# Fuente_lineal_12V_-12V_5V_-_500mA.net
KiCad netlist of a schematic drawn in EAGLE
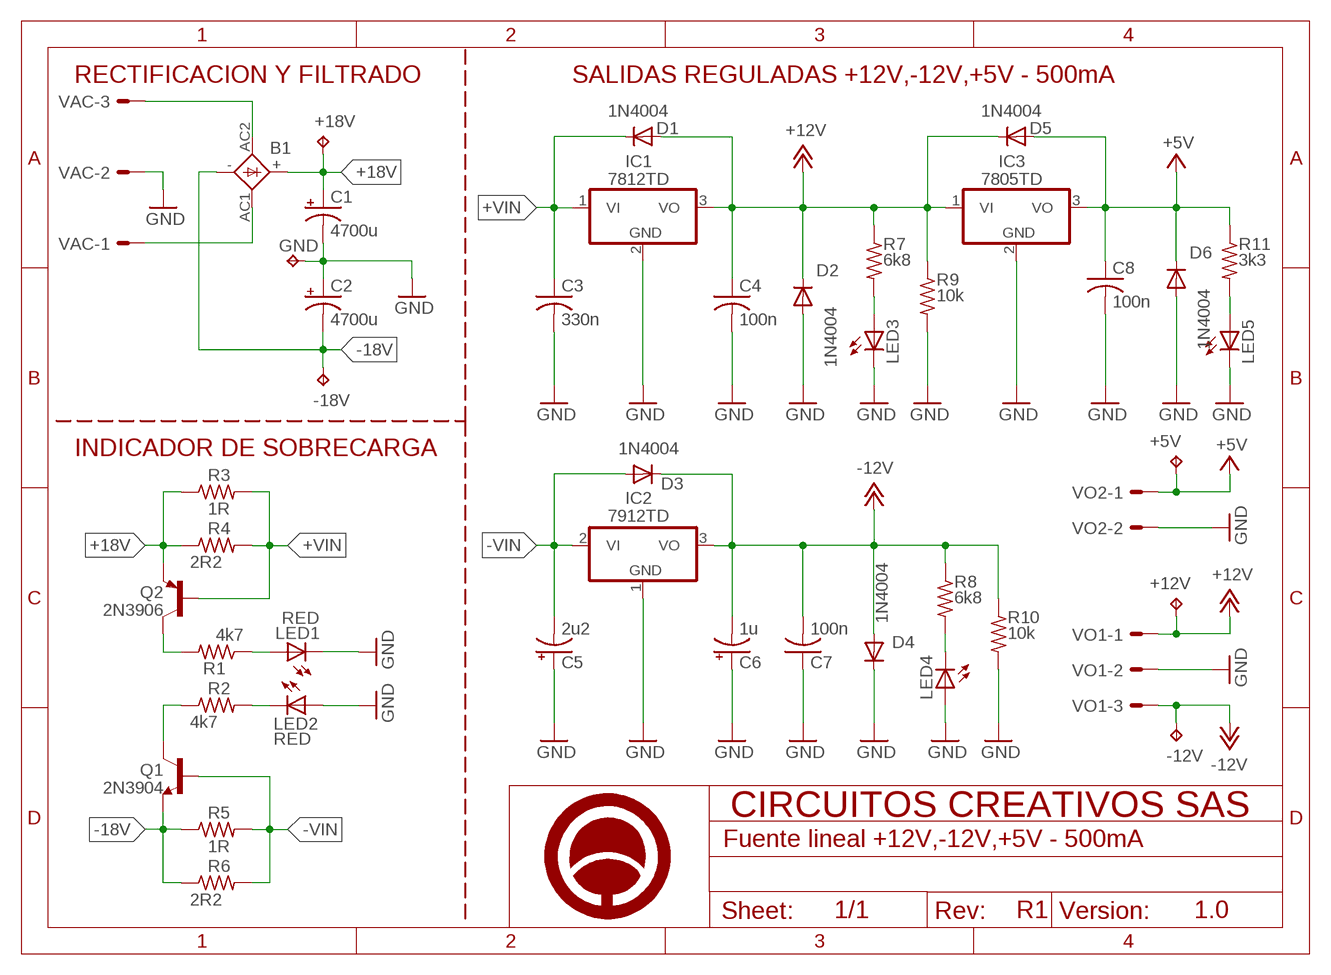
[diagram p0: schematic, sheet 1]

(export (version "E")
  (design (tool "Eeschema 10.0.6"))
  (components
    (comp (ref "+5V")
      (value "TPPAD1-17")
      (footprint "eagle-import:P1-17")
      (libsource (lib "eagle-import") (part "TPPAD1-17"))
    )
    (comp (ref "+12V")
      (value "TPPAD1-17")
      (footprint "eagle-import:P1-17")
      (libsource (lib "eagle-import") (part "TPPAD1-17"))
    )
    (comp (ref "+18V")
      (value "TPPAD1-17")
      (footprint "eagle-import:P1-17")
      (libsource (lib "eagle-import") (part "TPPAD1-17"))
    )
    (comp (ref "-12V")
      (value "TPPAD1-17")
      (footprint "eagle-import:P1-17")
      (libsource (lib "eagle-import") (part "TPPAD1-17"))
    )
    (comp (ref "-18V")
      (value "TPPAD1-17")
      (footprint "eagle-import:P1-17")
      (libsource (lib "eagle-import") (part "TPPAD1-17"))
    )
    (comp (ref "B1")
      (value "KBL")
      (footprint "eagle-import:KBL")
      (libsource (lib "eagle-import") (part "KBL"))
    )
    (comp (ref "C1")
      (value "4700u")
      (footprint "eagle-import:E7,5-16")
      (libsource (lib "eagle-import") (part "CPOL-USE7.5-16"))
    )
    (comp (ref "C2")
      (value "4700u")
      (footprint "eagle-import:E7,5-16")
      (libsource (lib "eagle-import") (part "CPOL-USE7.5-16"))
    )
    (comp (ref "C3")
      (value "330n")
      (footprint "eagle-import:C050-030X075")
      (libsource (lib "eagle-import") (part "C-US050-030X075"))
    )
    (comp (ref "C4")
      (value "100n")
      (footprint "eagle-import:C050-030X075")
      (libsource (lib "eagle-import") (part "C-US050-030X075"))
    )
    (comp (ref "C5")
      (value "2u2")
      (footprint "eagle-import:E2,5-6E")
      (libsource (lib "eagle-import") (part "CPOL-USE2,5-6E"))
    )
    (comp (ref "C6")
      (value "1u")
      (footprint "eagle-import:E2,5-6E")
      (libsource (lib "eagle-import") (part "CPOL-USE2,5-6E"))
    )
    (comp (ref "C7")
      (value "100n")
      (footprint "eagle-import:C050-030X075")
      (libsource (lib "eagle-import") (part "C-US050-030X075"))
    )
    (comp (ref "C8")
      (value "100n")
      (footprint "eagle-import:C050-030X075")
      (libsource (lib "eagle-import") (part "C-US050-030X075"))
    )
    (comp (ref "D1")
      (value "1N4004")
      (footprint "eagle-import:DO41-10")
      (libsource (lib "eagle-import") (part "1N4004"))
    )
    (comp (ref "D2")
      (value "1N4004")
      (footprint "eagle-import:DO41-10")
      (libsource (lib "eagle-import") (part "1N4004"))
    )
    (comp (ref "D3")
      (value "1N4004")
      (footprint "eagle-import:DO41-10")
      (libsource (lib "eagle-import") (part "1N4004"))
    )
    (comp (ref "D4")
      (value "1N4004")
      (footprint "eagle-import:DO41-10")
      (libsource (lib "eagle-import") (part "1N4004"))
    )
    (comp (ref "D5")
      (value "1N4004")
      (footprint "eagle-import:DO41-10")
      (libsource (lib "eagle-import") (part "1N4004"))
    )
    (comp (ref "D6")
      (value "1N4004")
      (footprint "eagle-import:DO41-10")
      (libsource (lib "eagle-import") (part "1N4004"))
    )
    (comp (ref "FRAME1")
      (value "A5_HORIZONTAL")
      (footprint "eagle-import:LOGO")
      (libsource (lib "eagle-import") (part "A5_HORIZONTAL"))
    )
    (comp (ref "GND")
      (value "TPPAD1-17")
      (footprint "eagle-import:P1-17")
      (libsource (lib "eagle-import") (part "TPPAD1-17"))
    )
    (comp (ref "IC1")
      (value "7812TD")
      (footprint "eagle-import:TO220VD")
      (libsource (lib "eagle-import") (part "78TD12"))
    )
    (comp (ref "IC2")
      (value "7912TD")
      (footprint "eagle-import:TO220VD")
      (libsource (lib "eagle-import") (part "79TD12"))
    )
    (comp (ref "IC3")
      (value "7805TD")
      (footprint "eagle-import:TO220VD")
      (libsource (lib "eagle-import") (part "78TD05"))
    )
    (comp (ref "LED1")
      (value "RED")
      (footprint "eagle-import:LED5MM")
      (libsource (lib "eagle-import") (part "LED5MM"))
    )
    (comp (ref "LED2")
      (value "RED")
      (footprint "eagle-import:LED5MM")
      (libsource (lib "eagle-import") (part "LED5MM"))
    )
    (comp (ref "LED3")
      (value "LED5MM")
      (footprint "eagle-import:LED5MM")
      (libsource (lib "eagle-import") (part "LED5MM"))
    )
    (comp (ref "LED4")
      (value "LED5MM")
      (footprint "eagle-import:LED5MM")
      (libsource (lib "eagle-import") (part "LED5MM"))
    )
    (comp (ref "LED5")
      (value "LED5MM")
      (footprint "eagle-import:LED5MM")
      (libsource (lib "eagle-import") (part "LED5MM"))
    )
    (comp (ref "Q1")
      (value "2N3904")
      (footprint "eagle-import:TO-92")
      (libsource (lib "eagle-import") (part "2N3904"))
    )
    (comp (ref "Q2")
      (value "2N3906")
      (footprint "eagle-import:TO-92")
      (libsource (lib "eagle-import") (part "2N3906"))
    )
    (comp (ref "R1")
      (value "4k7")
      (footprint "eagle-import:0204_7")
      (libsource (lib "eagle-import") (part "R-US_0204/7"))
    )
    (comp (ref "R2")
      (value "4k7")
      (footprint "eagle-import:0204_7")
      (libsource (lib "eagle-import") (part "R-US_0204/7"))
    )
    (comp (ref "R3")
      (value "1R")
      (footprint "eagle-import:0922_22")
      (libsource (lib "eagle-import") (part "R-US_0922/22"))
    )
    (comp (ref "R4")
      (value "2R2")
      (footprint "eagle-import:0922_22")
      (libsource (lib "eagle-import") (part "R-US_0922/22"))
    )
    (comp (ref "R5")
      (value "1R")
      (footprint "eagle-import:0922_22")
      (libsource (lib "eagle-import") (part "R-US_0922/22"))
    )
    (comp (ref "R6")
      (value "2R2")
      (footprint "eagle-import:0922_22")
      (libsource (lib "eagle-import") (part "R-US_0922/22"))
    )
    (comp (ref "R7")
      (value "6k8")
      (footprint "eagle-import:0204_7")
      (libsource (lib "eagle-import") (part "R-US_0204/7"))
    )
    (comp (ref "R8")
      (value "6k8")
      (footprint "eagle-import:0204_7")
      (libsource (lib "eagle-import") (part "R-US_0204/7"))
    )
    (comp (ref "R9")
      (value "10k")
      (footprint "eagle-import:0204_7")
      (libsource (lib "eagle-import") (part "R-US_0204/7"))
    )
    (comp (ref "R10")
      (value "10k")
      (footprint "eagle-import:0204_7")
      (libsource (lib "eagle-import") (part "R-US_0204/7"))
    )
    (comp (ref "R11")
      (value "3k3")
      (footprint "eagle-import:0204_7")
      (libsource (lib "eagle-import") (part "R-US_0204/7"))
    )
    (comp (ref "VAC")
      (value "KK-156-3")
      (footprint "eagle-import:KK-156-3")
      (libsource (lib "eagle-import") (part "KK-156-3"))
    )
    (comp (ref "VO1")
      (value "KK-156-3")
      (footprint "eagle-import:KK-156-3")
      (libsource (lib "eagle-import") (part "KK-156-3"))
    )
    (comp (ref "VO2")
      (value "KK-156-2")
      (footprint "eagle-import:KK-156-2")
      (libsource (lib "eagle-import") (part "KK-156-2"))
    )
  )
  (nets
    (net (code "1") (name "+5V") (class "Default")
      (node (ref "+5V") (pin "TP") (pinfunction "TP_TP") (pintype "input"))
      (node (ref "C8") (pin "1") (pinfunction "1_1") (pintype "passive"))
      (node (ref "D5") (pin "A") (pinfunction "A_A") (pintype "passive"))
      (node (ref "D6") (pin "C") (pinfunction "C_C") (pintype "passive"))
      (node (ref "IC3") (pin "3") (pinfunction "VO_3") (pintype "passive"))
      (node (ref "R11") (pin "1") (pinfunction "1_1") (pintype "passive"))
      (node (ref "VO2") (pin "1") (pinfunction "S_1") (pintype "passive"))
    )
    (net (code "2") (name "+12V") (class "Default")
      (node (ref "+12V") (pin "TP") (pinfunction "TP_TP") (pintype "input"))
      (node (ref "C4") (pin "1") (pinfunction "1_1") (pintype "passive"))
      (node (ref "D1") (pin "A") (pinfunction "A_A") (pintype "passive"))
      (node (ref "D2") (pin "C") (pinfunction "C_C") (pintype "passive"))
      (node (ref "D5") (pin "C") (pinfunction "C_C") (pintype "passive"))
      (node (ref "IC1") (pin "3") (pinfunction "VO_3") (pintype "passive"))
      (node (ref "IC3") (pin "1") (pinfunction "VI_1") (pintype "input"))
      (node (ref "R7") (pin "1") (pinfunction "1_1") (pintype "passive"))
      (node (ref "R9") (pin "1") (pinfunction "1_1") (pintype "passive"))
      (node (ref "VO1") (pin "1") (pinfunction "S_1") (pintype "passive"))
    )
    (net (code "3") (name "+18V") (class "Default")
      (node (ref "+18V") (pin "TP") (pinfunction "TP_TP") (pintype "input"))
      (node (ref "B1") (pin "+") (pinfunction "+_+") (pintype "passive"))
      (node (ref "C1") (pin "+") (pinfunction "+_+") (pintype "passive"))
      (node (ref "Q2") (pin "1") (pinfunction "E_1") (pintype "passive"))
      (node (ref "R3") (pin "1") (pinfunction "1_1") (pintype "passive"))
      (node (ref "R4") (pin "1") (pinfunction "1_1") (pintype "passive"))
    )
    (net (code "4") (name "+VIN") (class "Default")
      (node (ref "C3") (pin "1") (pinfunction "1_1") (pintype "passive"))
      (node (ref "D1") (pin "C") (pinfunction "C_C") (pintype "passive"))
      (node (ref "IC1") (pin "1") (pinfunction "VI_1") (pintype "input"))
      (node (ref "Q2") (pin "2") (pinfunction "B_2") (pintype "passive"))
      (node (ref "R3") (pin "2") (pinfunction "2_2") (pintype "passive"))
      (node (ref "R4") (pin "2") (pinfunction "2_2") (pintype "passive"))
    )
    (net (code "5") (name "-12V") (class "Default")
      (node (ref "-12V") (pin "TP") (pinfunction "TP_TP") (pintype "input"))
      (node (ref "C6") (pin "-") (pinfunction "-_-") (pintype "passive"))
      (node (ref "C7") (pin "2") (pinfunction "2_2") (pintype "passive"))
      (node (ref "D3") (pin "C") (pinfunction "C_C") (pintype "passive"))
      (node (ref "D4") (pin "A") (pinfunction "A_A") (pintype "passive"))
      (node (ref "IC2") (pin "3") (pinfunction "VO_3") (pintype "passive"))
      (node (ref "R10") (pin "1") (pinfunction "1_1") (pintype "passive"))
      (node (ref "R8") (pin "1") (pinfunction "1_1") (pintype "passive"))
      (node (ref "VO1") (pin "3") (pinfunction "S_3") (pintype "passive"))
    )
    (net (code "6") (name "-18V") (class "Default")
      (node (ref "-18V") (pin "TP") (pinfunction "TP_TP") (pintype "input"))
      (node (ref "B1") (pin "-") (pinfunction "-_-") (pintype "passive"))
      (node (ref "C2") (pin "-") (pinfunction "-_-") (pintype "passive"))
      (node (ref "Q1") (pin "1") (pinfunction "E_1") (pintype "passive"))
      (node (ref "R5") (pin "1") (pinfunction "1_1") (pintype "passive"))
      (node (ref "R6") (pin "1") (pinfunction "1_1") (pintype "passive"))
    )
    (net (code "7") (name "-VIN") (class "Default")
      (node (ref "C5") (pin "-") (pinfunction "-_-") (pintype "passive"))
      (node (ref "D3") (pin "A") (pinfunction "A_A") (pintype "passive"))
      (node (ref "IC2") (pin "2") (pinfunction "VI_2") (pintype "input"))
      (node (ref "Q1") (pin "2") (pinfunction "B_2") (pintype "passive"))
      (node (ref "R5") (pin "2") (pinfunction "2_2") (pintype "passive"))
      (node (ref "R6") (pin "2") (pinfunction "2_2") (pintype "passive"))
    )
    (net (code "8") (name "GND") (class "Default")
      (node (ref "C1") (pin "-") (pinfunction "-_-") (pintype "passive"))
      (node (ref "C2") (pin "+") (pinfunction "+_+") (pintype "passive"))
      (node (ref "C3") (pin "2") (pinfunction "2_2") (pintype "passive"))
      (node (ref "C4") (pin "2") (pinfunction "2_2") (pintype "passive"))
      (node (ref "C5") (pin "+") (pinfunction "+_+") (pintype "passive"))
      (node (ref "C6") (pin "+") (pinfunction "+_+") (pintype "passive"))
      (node (ref "C7") (pin "1") (pinfunction "1_1") (pintype "passive"))
      (node (ref "C8") (pin "2") (pinfunction "2_2") (pintype "passive"))
      (node (ref "D2") (pin "A") (pinfunction "A_A") (pintype "passive"))
      (node (ref "D4") (pin "C") (pinfunction "C_C") (pintype "passive"))
      (node (ref "D6") (pin "A") (pinfunction "A_A") (pintype "passive"))
      (node (ref "GND") (pin "TP") (pinfunction "TP_TP") (pintype "input"))
      (node (ref "IC1") (pin "2") (pinfunction "GND_2") (pintype "passive"))
      (node (ref "IC2") (pin "1") (pinfunction "GND_1") (pintype "passive"))
      (node (ref "IC3") (pin "2") (pinfunction "GND_2") (pintype "passive"))
      (node (ref "LED1") (pin "K") (pinfunction "C_K") (pintype "passive"))
      (node (ref "LED2") (pin "A") (pinfunction "A_A") (pintype "passive"))
      (node (ref "LED3") (pin "K") (pinfunction "C_K") (pintype "passive"))
      (node (ref "LED4") (pin "A") (pinfunction "A_A") (pintype "passive"))
      (node (ref "LED5") (pin "K") (pinfunction "C_K") (pintype "passive"))
      (node (ref "R10") (pin "2") (pinfunction "2_2") (pintype "passive"))
      (node (ref "R9") (pin "2") (pinfunction "2_2") (pintype "passive"))
      (node (ref "VAC") (pin "2") (pinfunction "S_2") (pintype "passive"))
      (node (ref "VO1") (pin "2") (pinfunction "S_2") (pintype "passive"))
      (node (ref "VO2") (pin "2") (pinfunction "S_2") (pintype "passive"))
    )
    (net (code "9") (name "Net-(B1-AC1)") (class "Default")
      (node (ref "B1") (pin "AC2") (pinfunction "AC1_AC2") (pintype "passive"))
      (node (ref "VAC") (pin "3") (pinfunction "S_3") (pintype "passive"))
    )
    (net (code "10") (name "Net-(B1-AC2)") (class "Default")
      (node (ref "B1") (pin "AC1") (pinfunction "AC2_AC1") (pintype "passive"))
      (node (ref "VAC") (pin "1") (pinfunction "S_1") (pintype "passive"))
    )
    (net (code "11") (name "Net-(LED1-PadA)") (class "Default")
      (node (ref "LED1") (pin "A") (pinfunction "A_A") (pintype "passive"))
      (node (ref "R1") (pin "1") (pinfunction "1_1") (pintype "passive"))
    )
    (net (code "12") (name "Net-(LED2-C)") (class "Default")
      (node (ref "LED2") (pin "K") (pinfunction "C_K") (pintype "passive"))
      (node (ref "R2") (pin "2") (pinfunction "2_2") (pintype "passive"))
    )
    (net (code "13") (name "Net-(LED3-PadA)") (class "Default")
      (node (ref "LED3") (pin "A") (pinfunction "A_A") (pintype "passive"))
      (node (ref "R7") (pin "2") (pinfunction "2_2") (pintype "passive"))
    )
    (net (code "14") (name "Net-(LED4-C)") (class "Default")
      (node (ref "LED4") (pin "K") (pinfunction "C_K") (pintype "passive"))
      (node (ref "R8") (pin "2") (pinfunction "2_2") (pintype "passive"))
    )
    (net (code "15") (name "Net-(LED5-PadA)") (class "Default")
      (node (ref "LED5") (pin "A") (pinfunction "A_A") (pintype "passive"))
      (node (ref "R11") (pin "2") (pinfunction "2_2") (pintype "passive"))
    )
    (net (code "16") (name "Net-(Q1-C)") (class "Default")
      (node (ref "Q1") (pin "3") (pinfunction "C_3") (pintype "passive"))
      (node (ref "R2") (pin "1") (pinfunction "1_1") (pintype "passive"))
    )
    (net (code "17") (name "Net-(Q2-C)") (class "Default")
      (node (ref "Q2") (pin "3") (pinfunction "C_3") (pintype "passive"))
      (node (ref "R1") (pin "2") (pinfunction "2_2") (pintype "passive"))
    )
  )
)
